# 2_drivers_e_Motores.net
KiCad netlist of a schematic drawn in Altium Designer
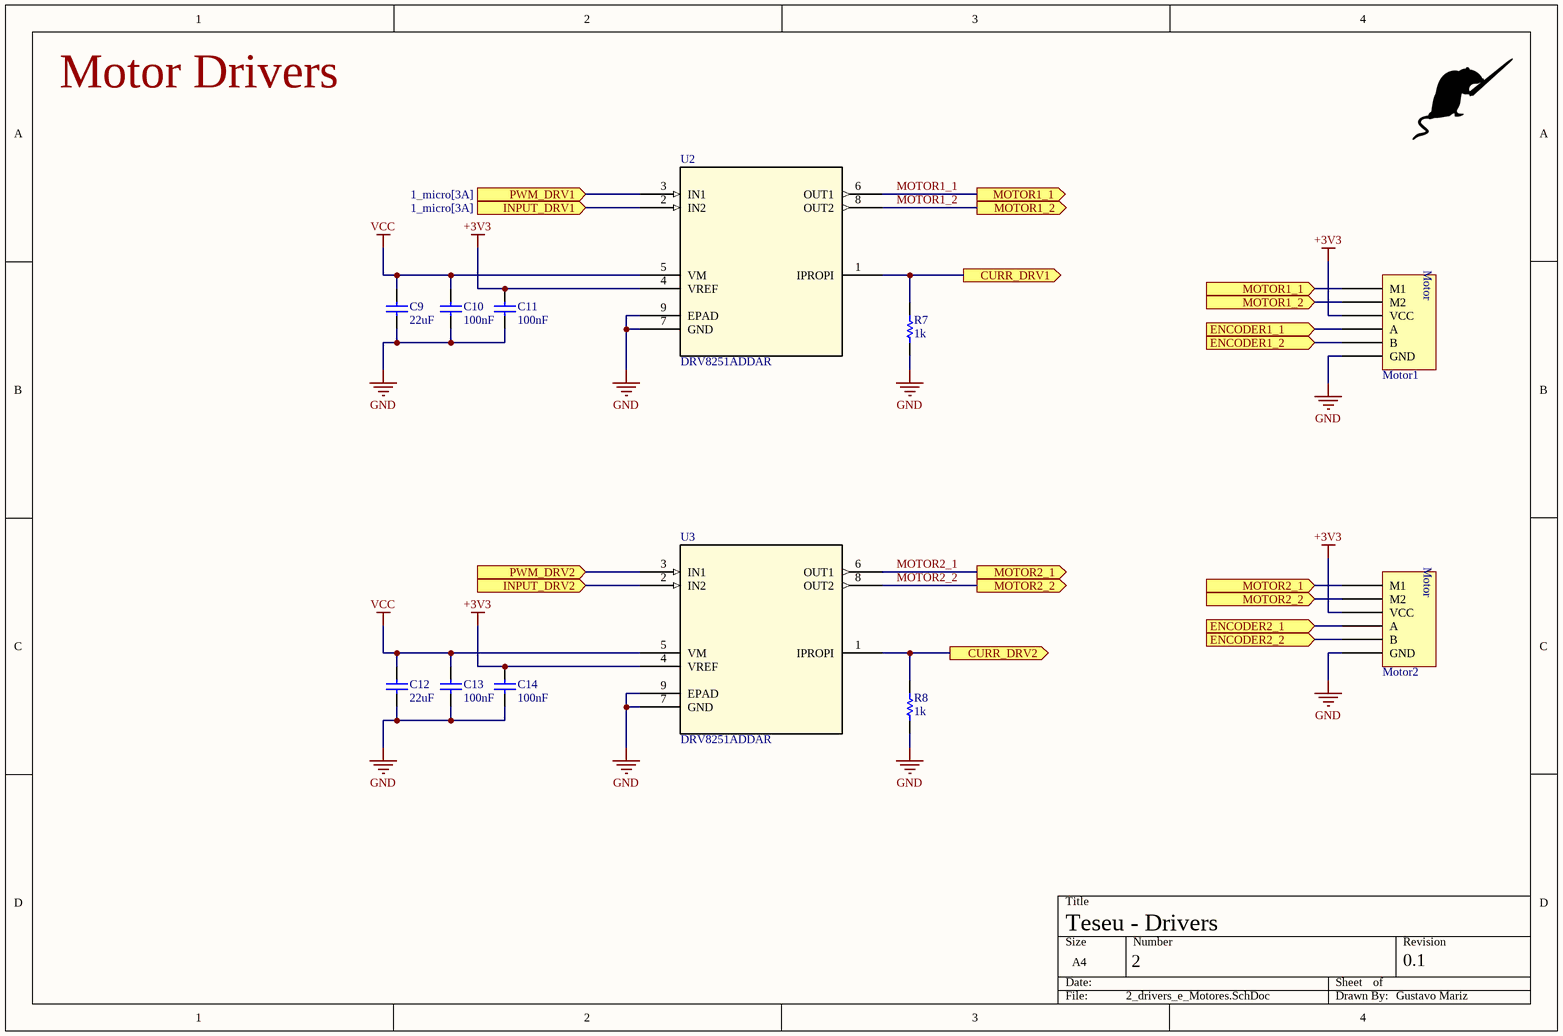
[diagram p0: 2_drivers_e_Motores.SchDoc]

(export (version "E")
  (design (tool "Eeschema 10.0.6"))
  (components
    (comp (ref "C9")
      (value "CAP")
      (footprint "CAP 0805")
      (description "Capacitor")
      (fields (field (name "VALOR") "22uF"))
      (libsource (lib "Biblioteca Trincabotz (1)") (part "CAP. CERÂMICO"))
    )
    (comp (ref "C10")
      (value "CAP")
      (footprint "0603")
      (description "Capacitor")
      (fields (field (name "VALOR") "100nF"))
      (libsource (lib "Biblioteca Trincabotz (1)") (part "CAP. CERÂMICO"))
    )
    (comp (ref "C11")
      (value "CAP")
      (footprint "0603")
      (description "Capacitor")
      (fields (field (name "VALOR") "100nF"))
      (libsource (lib "Biblioteca Trincabotz (1)") (part "CAP. CERÂMICO"))
    )
    (comp (ref "C12")
      (value "CAP")
      (footprint "CAP 0805")
      (description "Capacitor")
      (fields (field (name "VALOR") "22uF"))
      (libsource (lib "Biblioteca Trincabotz (1)") (part "CAP. CERÂMICO"))
    )
    (comp (ref "C13")
      (value "CAP")
      (footprint "0603")
      (description "Capacitor")
      (fields (field (name "VALOR") "100nF"))
      (libsource (lib "Biblioteca Trincabotz (1)") (part "CAP. CERÂMICO"))
    )
    (comp (ref "C14")
      (value "CAP")
      (footprint "0603")
      (description "Capacitor")
      (fields (field (name "VALOR") "100nF"))
      (libsource (lib "Biblioteca Trincabotz (1)") (part "CAP. CERÂMICO"))
    )
    (comp (ref "Motor1")
      (value "Micro Motor c/ Encoder")
      (footprint "Micro Metal c/ Encoder")
      (libsource (lib "Biblioteca de SCH") (part "Micro Motor c/ Encoder"))
    )
    (comp (ref "Motor2")
      (value "Micro Motor c/ Encoder")
      (footprint "Micro Metal c/ Encoder")
      (libsource (lib "Biblioteca de SCH") (part "Micro Motor c/ Encoder"))
    )
    (comp (ref "R7")
      (value "1k")
      (footprint "RES 0603")
      (description "Resistor")
      (fields (field (name "Comment") "RESISTOR"))
      (libsource (lib "Biblioteca Trincabotz (1)") (part "RESISTOR"))
    )
    (comp (ref "R8")
      (value "1k")
      (footprint "RES 0603")
      (description "Resistor")
      (fields (field (name "Comment") "RESISTOR"))
      (libsource (lib "Biblioteca Trincabotz (1)") (part "RESISTOR"))
    )
    (comp (ref "U2")
      (value "DRV8251ADDAR")
      (footprint "SOIC8_DDA_TEX")
      (description "No Description Available")
      (libsource (lib "DRV8251ADDAR") (part "DRV8251ADDAR"))
    )
    (comp (ref "U3")
      (value "DRV8251ADDAR")
      (footprint "SOIC8_DDA_TEX")
      (description "No Description Available")
      (libsource (lib "DRV8251ADDAR") (part "DRV8251ADDAR"))
    )
  )
  (nets
    (net (code "1") (name "+3V3") (class "Default")
      (node (ref "C11") (pin "2") (pinfunction "2_2") (pintype "passive"))
      (node (ref "C14") (pin "2") (pinfunction "2_2") (pintype "passive"))
      (node (ref "Motor1") (pin "4") (pinfunction "VCC_4") (pintype "passive"))
      (node (ref "Motor2") (pin "4") (pinfunction "VCC_4") (pintype "passive"))
      (node (ref "U2") (pin "4") (pinfunction "VREF_4") (pintype "power_in"))
      (node (ref "U3") (pin "4") (pinfunction "VREF_4") (pintype "power_in"))
    )
    (net (code "2") (name "/CURR_DRV1") (class "Default")
      (node (ref "R7") (pin "2") (pinfunction "2_2") (pintype "passive"))
      (node (ref "U2") (pin "1") (pinfunction "IPROPI_1") (pintype "power_in"))
    )
    (net (code "3") (name "/CURR_DRV2") (class "Default")
      (node (ref "R8") (pin "2") (pinfunction "2_2") (pintype "passive"))
      (node (ref "U3") (pin "1") (pinfunction "IPROPI_1") (pintype "power_in"))
    )
    (net (code "4") (name "/ENCODER1_1") (class "Default")
      (node (ref "Motor1") (pin "3") (pinfunction "A_3") (pintype "passive"))
    )
    (net (code "5") (name "/ENCODER1_2") (class "Default")
      (node (ref "Motor1") (pin "2") (pinfunction "B_2") (pintype "passive"))
    )
    (net (code "6") (name "/ENCODER2_1") (class "Default")
      (node (ref "Motor2") (pin "3") (pinfunction "A_3") (pintype "passive"))
    )
    (net (code "7") (name "/ENCODER2_2") (class "Default")
      (node (ref "Motor2") (pin "2") (pinfunction "B_2") (pintype "passive"))
    )
    (net (code "8") (name "/INPUT_DRV1") (class "Default")
      (node (ref "U2") (pin "2") (pinfunction "IN2_2") (pintype "input"))
    )
    (net (code "9") (name "/INPUT_DRV2") (class "Default")
      (node (ref "U3") (pin "2") (pinfunction "IN2_2") (pintype "input"))
    )
    (net (code "10") (name "/MOTOR1_1") (class "Default")
      (node (ref "Motor1") (pin "6") (pinfunction "M1_6") (pintype "passive"))
      (node (ref "U2") (pin "6") (pinfunction "OUT1_6") (pintype "output"))
    )
    (net (code "11") (name "/MOTOR1_2") (class "Default")
      (node (ref "Motor1") (pin "5") (pinfunction "M2_5") (pintype "passive"))
      (node (ref "U2") (pin "8") (pinfunction "OUT2_8") (pintype "output"))
    )
    (net (code "12") (name "/MOTOR2_1") (class "Default")
      (node (ref "Motor2") (pin "6") (pinfunction "M1_6") (pintype "passive"))
      (node (ref "U3") (pin "6") (pinfunction "OUT1_6") (pintype "output"))
    )
    (net (code "13") (name "/MOTOR2_2") (class "Default")
      (node (ref "Motor2") (pin "5") (pinfunction "M2_5") (pintype "passive"))
      (node (ref "U3") (pin "8") (pinfunction "OUT2_8") (pintype "output"))
    )
    (net (code "14") (name "/PWM_DRV1") (class "Default")
      (node (ref "U2") (pin "3") (pinfunction "IN1_3") (pintype "input"))
    )
    (net (code "15") (name "/PWM_DRV2") (class "Default")
      (node (ref "U3") (pin "3") (pinfunction "IN1_3") (pintype "input"))
    )
    (net (code "16") (name "GND") (class "Default")
      (node (ref "C10") (pin "1") (pinfunction "1_1") (pintype "passive"))
      (node (ref "C11") (pin "1") (pinfunction "1_1") (pintype "passive"))
      (node (ref "C12") (pin "1") (pinfunction "1_1") (pintype "passive"))
      (node (ref "C13") (pin "1") (pinfunction "1_1") (pintype "passive"))
      (node (ref "C14") (pin "1") (pinfunction "1_1") (pintype "passive"))
      (node (ref "C9") (pin "1") (pinfunction "1_1") (pintype "passive"))
      (node (ref "Motor1") (pin "1") (pinfunction "GND_1") (pintype "passive"))
      (node (ref "Motor2") (pin "1") (pinfunction "GND_1") (pintype "passive"))
      (node (ref "R7") (pin "1") (pinfunction "1_1") (pintype "passive"))
      (node (ref "R8") (pin "1") (pinfunction "1_1") (pintype "passive"))
      (node (ref "U2") (pin "7") (pinfunction "GND_7") (pintype "power_in"))
      (node (ref "U2") (pin "9") (pinfunction "EPAD_9") (pintype "power_in"))
      (node (ref "U3") (pin "7") (pinfunction "GND_7") (pintype "power_in"))
      (node (ref "U3") (pin "9") (pinfunction "EPAD_9") (pintype "power_in"))
    )
    (net (code "17") (name "VCC") (class "Default")
      (node (ref "C10") (pin "2") (pinfunction "2_2") (pintype "passive"))
      (node (ref "C12") (pin "2") (pinfunction "2_2") (pintype "passive"))
      (node (ref "C13") (pin "2") (pinfunction "2_2") (pintype "passive"))
      (node (ref "C9") (pin "2") (pinfunction "2_2") (pintype "passive"))
      (node (ref "U2") (pin "5") (pinfunction "VM_5") (pintype "power_in"))
      (node (ref "U3") (pin "5") (pinfunction "VM_5") (pintype "power_in"))
    )
  )
)
